# tester.net
KiCad netlist of a schematic drawn in EAGLE
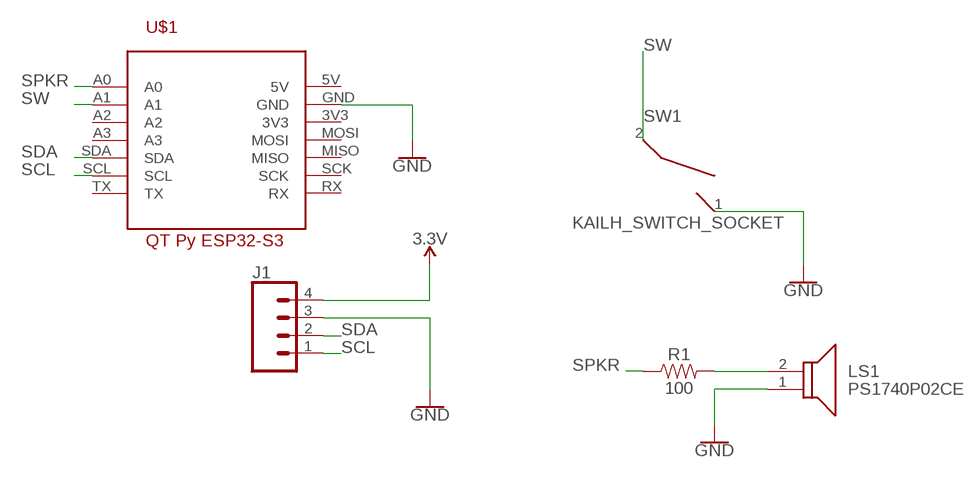
[diagram p0: schematic, sheet 1]

(export (version "E")
  (design (tool "Eeschema 10.0.6"))
  (components
    (comp (ref "J1")
      (value "CONN_04")
      (footprint "eagle-import:1X04")
      (libsource (lib "eagle-import") (part "CONN_04"))
    )
    (comp (ref "LS1")
      (value "PS1740P02CE")
      (footprint "eagle-import:PS1740P02CE")
      (fields (field (name "MOUSER_PART_NUMBER") "810-PS1740P02CE"))
      (libsource (lib "eagle-import") (part "PS1740P02CE"))
    )
    (comp (ref "R1")
      (value "100")
      (footprint "eagle-import:AXIAL-0.3")
      (libsource (lib "eagle-import") (part "100OHM-HORIZ-1/4W-1%"))
    )
    (comp (ref "SW1")
      (value "KAILH_SWITCH_SOCKET")
      (footprint "eagle-import:SWITCH_SOCKET")
      (libsource (lib "eagle-import") (part "KAILH_SWITCH_SOCKET"))
    )
    (comp (ref "U1")
      (value "QTPY-ESP32-S3")
      (footprint "eagle-import:QTPY-ESP32-S3")
      (libsource (lib "eagle-import") (part "QTPY-ESP32-S3"))
    )
  )
  (nets
    (net (code "1") (name "/5V") (class "Default")
      (node (ref "U1") (pin "5V") (pinfunction "5V_5V") (pintype "power_in"))
    )
    (net (code "2") (name "/SCL") (class "Default")
      (node (ref "J1") (pin "1") (pinfunction "1_1") (pintype "passive"))
      (node (ref "U1") (pin "SCL") (pinfunction "SCL_SCL") (pintype "bidirectional"))
    )
    (net (code "3") (name "/SDA") (class "Default")
      (node (ref "J1") (pin "2") (pinfunction "2_2") (pintype "passive"))
      (node (ref "U1") (pin "SDA") (pinfunction "SDA_SDA") (pintype "bidirectional"))
    )
    (net (code "4") (name "/SPKR") (class "Default")
      (node (ref "R1") (pin "P$1") (pinfunction "1_P$1") (pintype "passive"))
      (node (ref "U1") (pin "A0") (pinfunction "A0_A0") (pintype "bidirectional"))
    )
    (net (code "5") (name "/SW") (class "Default")
      (node (ref "SW1") (pin "2") (pinfunction "1_2") (pintype "passive"))
      (node (ref "U1") (pin "A1") (pinfunction "A1_A1") (pintype "bidirectional"))
    )
    (net (code "6") (name "3.3V") (class "Default")
      (node (ref "J1") (pin "4") (pinfunction "4_4") (pintype "passive"))
    )
    (net (code "7") (name "GND") (class "Default")
      (node (ref "J1") (pin "3") (pinfunction "3_3") (pintype "passive"))
      (node (ref "LS1") (pin "1") (pinfunction "GND_1") (pintype "bidirectional"))
      (node (ref "SW1") (pin "1") (pinfunction "2_1") (pintype "passive"))
      (node (ref "U1") (pin "GND") (pinfunction "GND_GND") (pintype "power_in"))
    )
    (net (code "8") (name "Net-(LS1-VCC)") (class "Default")
      (node (ref "LS1") (pin "2") (pinfunction "VCC_2") (pintype "bidirectional"))
      (node (ref "R1") (pin "P$2") (pinfunction "2_P$2") (pintype "passive"))
    )
    (net (code "9") (name "unconnected-(U1-Pad3V3)") (class "Default")
      (node (ref "U1") (pin "3V3") (pinfunction "3V3_3V3") (pintype "bidirectional"))
    )
    (net (code "10") (name "unconnected-(U1-PadA2)") (class "Default")
      (node (ref "U1") (pin "A2") (pinfunction "A2_A2") (pintype "bidirectional"))
    )
    (net (code "11") (name "unconnected-(U1-PadA3)") (class "Default")
      (node (ref "U1") (pin "A3") (pinfunction "A3_A3") (pintype "bidirectional"))
    )
    (net (code "12") (name "unconnected-(U1-PadMISO)") (class "Default")
      (node (ref "U1") (pin "MISO") (pinfunction "MISO_MISO") (pintype "bidirectional"))
    )
    (net (code "13") (name "unconnected-(U1-PadMOSI)") (class "Default")
      (node (ref "U1") (pin "MOSI") (pinfunction "MOSI_MOSI") (pintype "bidirectional"))
    )
    (net (code "14") (name "unconnected-(U1-PadRX)") (class "Default")
      (node (ref "U1") (pin "RX") (pinfunction "RX_RX") (pintype "bidirectional"))
    )
    (net (code "15") (name "unconnected-(U1-PadSCK)") (class "Default")
      (node (ref "U1") (pin "SCK") (pinfunction "SCK_SCK") (pintype "bidirectional"))
    )
    (net (code "16") (name "unconnected-(U1-PadTX)") (class "Default")
      (node (ref "U1") (pin "TX") (pinfunction "TX_TX") (pintype "bidirectional"))
    )
  )
)
